# ANALOG_IO.net
KiCad netlist of a schematic drawn in Altium Designer
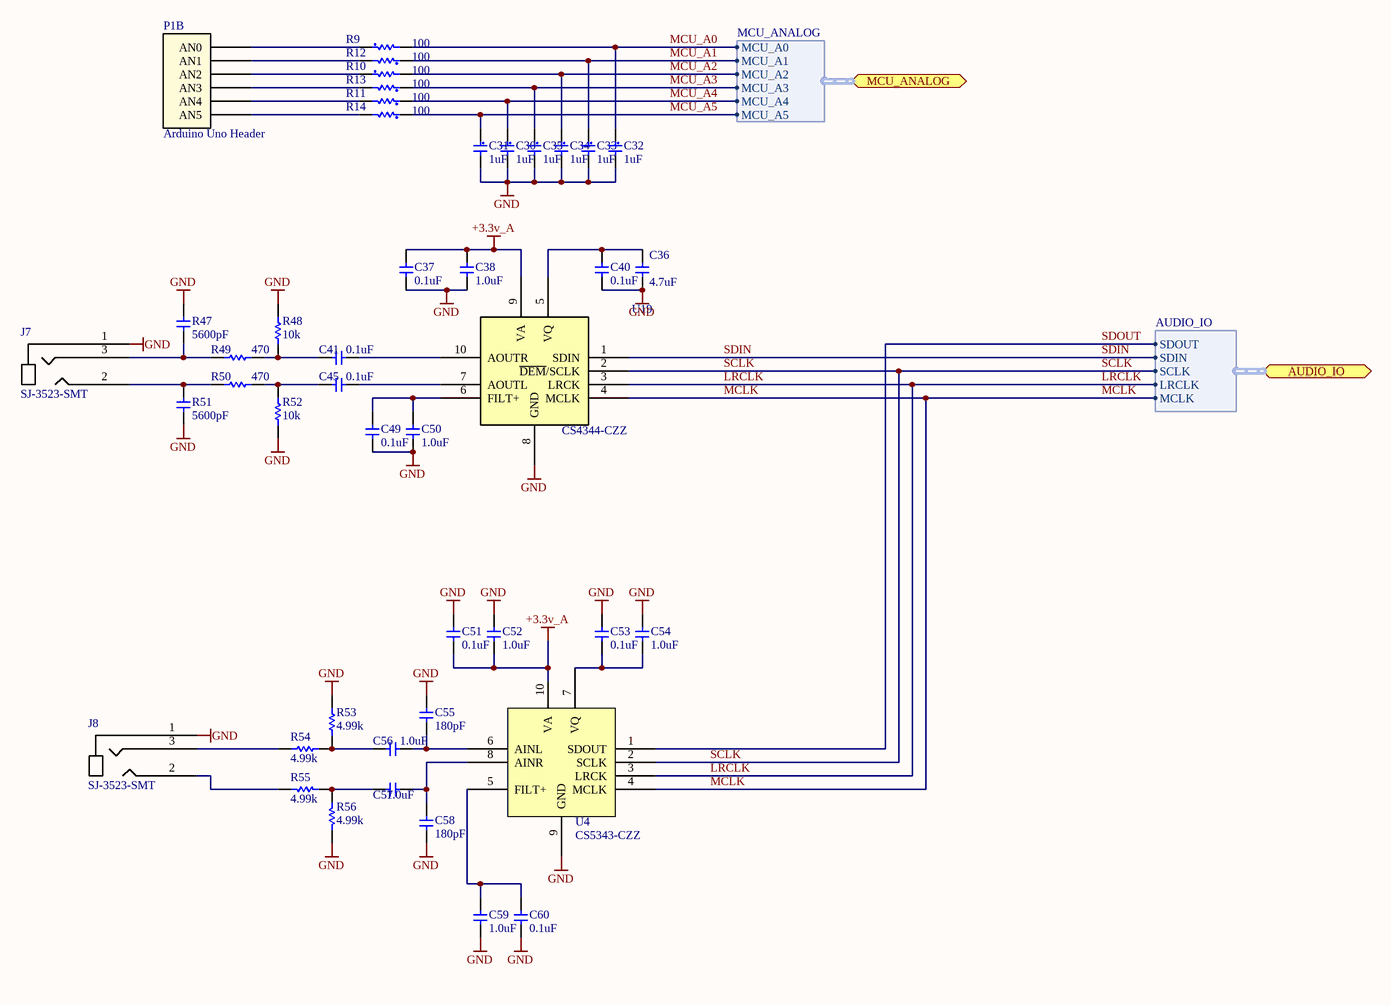
[diagram p0: ANALOG_IO.SchDoc]

(export (version "E")
  (design (tool "Eeschema 10.0.6"))
  (components
    (comp (ref "C30")
      (value "1uF")
      (footprint "C0603")
      (description "CAP CER .1UF 50V 10% X7R 0603")
      (fields
        (field (name "MANUFACTURER") "Murata Electronics North America")
        (field (name "MANUFACTURER PART NUMBER") "GRM188R71H104KA93D")
      )
      (libsource (lib "myGeneral") (part "Cap-Eli"))
    )
    (comp (ref "C31")
      (value "1uF")
      (footprint "C0603")
      (description "CAP CER .1UF 50V 10% X7R 0603")
      (fields
        (field (name "MANUFACTURER") "Murata Electronics North America")
        (field (name "MANUFACTURER PART NUMBER") "GRM188R71H104KA93D")
      )
      (libsource (lib "myGeneral") (part "Cap-Eli"))
    )
    (comp (ref "C32")
      (value "1uF")
      (footprint "C0603")
      (description "CAP CER .1UF 50V 10% X7R 0603")
      (fields
        (field (name "MANUFACTURER") "Murata Electronics North America")
        (field (name "MANUFACTURER PART NUMBER") "GRM188R71H104KA93D")
      )
      (libsource (lib "myGeneral") (part "Cap-Eli"))
    )
    (comp (ref "C33")
      (value "1uF")
      (footprint "C0603")
      (description "CAP CER .1UF 50V 10% X7R 0603")
      (fields
        (field (name "MANUFACTURER") "Murata Electronics North America")
        (field (name "MANUFACTURER PART NUMBER") "GRM188R71H104KA93D")
      )
      (libsource (lib "myGeneral") (part "Cap-Eli"))
    )
    (comp (ref "C34")
      (value "1uF")
      (footprint "C0603")
      (description "CAP CER .1UF 50V 10% X7R 0603")
      (fields
        (field (name "MANUFACTURER") "Murata Electronics North America")
        (field (name "MANUFACTURER PART NUMBER") "GRM188R71H104KA93D")
      )
      (libsource (lib "myGeneral") (part "Cap-Eli"))
    )
    (comp (ref "C35")
      (value "1uF")
      (footprint "C0603")
      (description "CAP CER .1UF 50V 10% X7R 0603")
      (fields
        (field (name "MANUFACTURER") "Murata Electronics North America")
        (field (name "MANUFACTURER PART NUMBER") "GRM188R71H104KA93D")
      )
      (libsource (lib "myGeneral") (part "Cap-Eli"))
    )
    (comp (ref "C36")
      (value "4.7uF")
      (footprint "C0603")
      (description "CAP CER 4.7UF 6.3V X5R 0603")
      (fields
        (field (name "MANUFACTURER") "Murata Electronics North America")
        (field (name "MANUFACTURER PART NUMBER") "GRM188R60J475KE19D")
      )
      (libsource (lib "eCapacitors") (part "GRM188R60J475KE19D"))
    )
    (comp (ref "C37")
      (value "0.1uF")
      (footprint "C0603")
      (description "CAP CER .1UF 50V 10% X7R 0603")
      (fields
        (field (name "MANUFACTURER") "Murata Electronics North America")
        (field (name "MANUFACTURER PART NUMBER") "GRM188R71H104KA93D")
      )
      (libsource (lib "eCapacitors") (part "GRM188R71H104KA93D"))
    )
    (comp (ref "C38")
      (value "1.0uF")
      (footprint "C0805")
      (description "CAP CER 1.0UF 16V 10% X7R 0805")
      (fields
        (field (name "MANUFACTURER") "Murata Electronics North America")
        (field (name "MANUFACTURER PART NUMBER") "GRM21BR71C105KA01L")
      )
      (libsource (lib "eCapacitors") (part "GRM21BR71C105KA01L"))
    )
    (comp (ref "C40")
      (value "0.1uF")
      (footprint "C0603")
      (description "CAP CER .1UF 50V 10% X7R 0603")
      (fields
        (field (name "MANUFACTURER") "Murata Electronics North America")
        (field (name "MANUFACTURER PART NUMBER") "GRM188R71H104KA93D")
      )
      (libsource (lib "eCapacitors") (part "GRM188R71H104KA93D"))
    )
    (comp (ref "C41")
      (value "0.1uF")
      (footprint "C0603")
      (description "CAP CER .1UF 50V 10% X7R 0603")
      (fields
        (field (name "MANUFACTURER") "Murata Electronics North America")
        (field (name "MANUFACTURER PART NUMBER") "GRM188R71H104KA93D")
      )
      (libsource (lib "eCapacitors") (part "GRM188R71H104KA93D"))
    )
    (comp (ref "C45")
      (value "0.1uF")
      (footprint "C0603")
      (description "CAP CER .1UF 50V 10% X7R 0603")
      (fields
        (field (name "MANUFACTURER") "Murata Electronics North America")
        (field (name "MANUFACTURER PART NUMBER") "GRM188R71H104KA93D")
      )
      (libsource (lib "eCapacitors") (part "GRM188R71H104KA93D"))
    )
    (comp (ref "C49")
      (value "0.1uF")
      (footprint "C0603")
      (description "CAP CER .1UF 50V 10% X7R 0603")
      (fields
        (field (name "MANUFACTURER") "Murata Electronics North America")
        (field (name "MANUFACTURER PART NUMBER") "GRM188R71H104KA93D")
      )
      (libsource (lib "eCapacitors") (part "GRM188R71H104KA93D"))
    )
    (comp (ref "C50")
      (value "1.0uF")
      (footprint "C0805")
      (description "CAP CER 1.0UF 16V 10% X7R 0805")
      (fields
        (field (name "MANUFACTURER") "Murata Electronics North America")
        (field (name "MANUFACTURER PART NUMBER") "GRM21BR71C105KA01L")
      )
      (libsource (lib "eCapacitors") (part "GRM21BR71C105KA01L"))
    )
    (comp (ref "C51")
      (value "0.1uF")
      (footprint "C0603")
      (description "CAP CER .1UF 50V 10% X7R 0603")
      (fields
        (field (name "MANUFACTURER") "Murata Electronics North America")
        (field (name "MANUFACTURER PART NUMBER") "GRM188R71H104KA93D")
      )
      (libsource (lib "eCapacitors") (part "GRM188R71H104KA93D"))
    )
    (comp (ref "C52")
      (value "1.0uF")
      (footprint "C0805")
      (description "CAP CER 1.0UF 16V 10% X7R 0805")
      (fields
        (field (name "MANUFACTURER") "Murata Electronics North America")
        (field (name "MANUFACTURER PART NUMBER") "GRM21BR71C105KA01L")
      )
      (libsource (lib "eCapacitors") (part "GRM21BR71C105KA01L"))
    )
    (comp (ref "C53")
      (value "0.1uF")
      (footprint "C0603")
      (description "CAP CER .1UF 50V 10% X7R 0603")
      (fields
        (field (name "MANUFACTURER") "Murata Electronics North America")
        (field (name "MANUFACTURER PART NUMBER") "GRM188R71H104KA93D")
      )
      (libsource (lib "eCapacitors") (part "GRM188R71H104KA93D"))
    )
    (comp (ref "C54")
      (value "1.0uF")
      (footprint "C0805")
      (description "CAP CER 1.0UF 16V 10% X7R 0805")
      (fields
        (field (name "MANUFACTURER") "Murata Electronics North America")
        (field (name "MANUFACTURER PART NUMBER") "GRM21BR71C105KA01L")
      )
      (libsource (lib "eCapacitors") (part "GRM21BR71C105KA01L"))
    )
    (comp (ref "C55")
      (value "180pF")
      (footprint "C0603")
      (description "CAP CER 180PF 50V 5% NP0 0603")
      (fields
        (field (name "MANUFACTURER") "TDK Corporation")
        (field (name "MANUFACTURER PART NUMBER") "C1608C0G1H181J")
      )
      (libsource (lib "eCapacitors") (part "C1608C0G1H181J"))
    )
    (comp (ref "C56")
      (value "1.0uF")
      (footprint "C0805")
      (description "CAP CER 1.0UF 16V 10% X7R 0805")
      (fields
        (field (name "MANUFACTURER") "Murata Electronics North America")
        (field (name "MANUFACTURER PART NUMBER") "GRM21BR71C105KA01L")
      )
      (libsource (lib "eCapacitors") (part "GRM21BR71C105KA01L"))
    )
    (comp (ref "C57")
      (value "1.0uF")
      (footprint "C0805")
      (description "CAP CER 1.0UF 16V 10% X7R 0805")
      (fields
        (field (name "MANUFACTURER") "Murata Electronics North America")
        (field (name "MANUFACTURER PART NUMBER") "GRM21BR71C105KA01L")
      )
      (libsource (lib "eCapacitors") (part "GRM21BR71C105KA01L"))
    )
    (comp (ref "C58")
      (value "180pF")
      (footprint "C0603")
      (description "CAP CER 180PF 50V 5% NP0 0603")
      (fields
        (field (name "MANUFACTURER") "TDK Corporation")
        (field (name "MANUFACTURER PART NUMBER") "C1608C0G1H181J")
      )
      (libsource (lib "eCapacitors") (part "C1608C0G1H181J"))
    )
    (comp (ref "C59")
      (value "1.0uF")
      (footprint "C0805")
      (description "CAP CER 1.0UF 16V 10% X7R 0805")
      (fields
        (field (name "MANUFACTURER") "Murata Electronics North America")
        (field (name "MANUFACTURER PART NUMBER") "GRM21BR71C105KA01L")
      )
      (libsource (lib "eCapacitors") (part "GRM21BR71C105KA01L"))
    )
    (comp (ref "C60")
      (value "0.1uF")
      (footprint "C0603")
      (description "CAP CER .1UF 50V 10% X7R 0603")
      (fields
        (field (name "MANUFACTURER") "Murata Electronics North America")
        (field (name "MANUFACTURER PART NUMBER") "GRM188R71H104KA93D")
      )
      (libsource (lib "eCapacitors") (part "GRM188R71H104KA93D"))
    )
    (comp (ref "J7")
      (value "SJ-3523-SMT")
      (footprint "SJ-3523-SMT")
      (description "CONN AUDIO JACK 3.5MM STEREO SMD")
      (fields (field (name "MANUFACTURER") "CUI Inc") (field (name "SOURCE") "Digikey"))
      (libsource (lib "eConnector") (part "SJ-3523-SMT"))
    )
    (comp (ref "J8")
      (value "SJ-3523-SMT")
      (footprint "SJ-3523-SMT")
      (description "CONN AUDIO JACK 3.5MM STEREO SMD")
      (fields (field (name "MANUFACTURER") "CUI Inc") (field (name "SOURCE") "Digikey"))
      (libsource (lib "eConnector") (part "SJ-3523-SMT"))
    )
    (comp (ref "P1")
      (value "Arduino Uno Header")
      (footprint "Arduino Shield")
      (description "Arduino Duem Header")
      (libsource (lib "eConnector") (part "Arduino Shield"))
    )
    (comp (ref "R9")
      (value "100")
      (footprint "R0603")
      (description "RES 10.0K OHM 1/10W 1% 0603 SMD")
      (fields
        (field (name "MANUFACTURER") "Panasonic - ECG")
        (field (name "MANUFACTURER PART NUMBER") "ERJ-3EKF1002V")
      )
      (libsource (lib "myGeneral") (part "Res-Eli"))
    )
    (comp (ref "R10")
      (value "100")
      (footprint "R0603")
      (description "RES 10.0K OHM 1/10W 1% 0603 SMD")
      (fields
        (field (name "MANUFACTURER") "Panasonic - ECG")
        (field (name "MANUFACTURER PART NUMBER") "ERJ-3EKF1002V")
      )
      (libsource (lib "myGeneral") (part "Res-Eli"))
    )
    (comp (ref "R11")
      (value "100")
      (footprint "R0603")
      (description "RES 10.0K OHM 1/10W 1% 0603 SMD")
      (fields
        (field (name "MANUFACTURER") "Panasonic - ECG")
        (field (name "MANUFACTURER PART NUMBER") "ERJ-3EKF1002V")
      )
      (libsource (lib "myGeneral") (part "Res-Eli"))
    )
    (comp (ref "R12")
      (value "100")
      (footprint "R0603")
      (description "RES 10.0K OHM 1/10W 1% 0603 SMD")
      (fields
        (field (name "MANUFACTURER") "Panasonic - ECG")
        (field (name "MANUFACTURER PART NUMBER") "ERJ-3EKF1002V")
      )
      (libsource (lib "myGeneral") (part "Res-Eli"))
    )
    (comp (ref "R13")
      (value "100")
      (footprint "R0603")
      (description "RES 10.0K OHM 1/10W 1% 0603 SMD")
      (fields
        (field (name "MANUFACTURER") "Panasonic - ECG")
        (field (name "MANUFACTURER PART NUMBER") "ERJ-3EKF1002V")
      )
      (libsource (lib "myGeneral") (part "Res-Eli"))
    )
    (comp (ref "R14")
      (value "100")
      (footprint "R0603")
      (description "RES 10.0K OHM 1/10W 1% 0603 SMD")
      (fields
        (field (name "MANUFACTURER") "Panasonic - ECG")
        (field (name "MANUFACTURER PART NUMBER") "ERJ-3EKF1002V")
      )
      (libsource (lib "myGeneral") (part "Res-Eli"))
    )
    (comp (ref "R47")
      (value "5600pF")
      (footprint "C0603")
      (description "CAP CER 5600PF 50V 10% X7R 0603")
      (fields
        (field (name "MANUFACTURER") "Murata Electronics North America")
        (field (name "MANUFACTURER PART NUMBER") "GRM188R71H562KA01D")
      )
      (libsource (lib "eCapacitors") (part "GRM188R71H562KA01D"))
    )
    (comp (ref "R48")
      (value "10k")
      (footprint "R0603")
      (description "RES 10.0K OHM 1/10W 1% 0603 SMD")
      (fields
        (field (name "MANUFACTURER") "Panasonic - ECG")
        (field (name "TOLERANCE") "±1%")
        (field (name "SOURCE") "Digikey")
      )
      (libsource (lib "eRCL") (part "ERJ-3EKF1002V"))
    )
    (comp (ref "R49")
      (value "470")
      (footprint "R0603")
      (description "RES 470 OHM 1/10W 1% 0603 SMD")
      (fields
        (field (name "MANUFACTURER") "Panasonic - ECG")
        (field (name "MANUFACTURER PART NUMBER") "ERJ-3EKF4700V")
      )
      (libsource (lib "eResistors") (part "ERJ-3EKF4700V"))
    )
    (comp (ref "R50")
      (value "470")
      (footprint "R0603")
      (description "RES 470 OHM 1/10W 1% 0603 SMD")
      (fields
        (field (name "MANUFACTURER") "Panasonic - ECG")
        (field (name "MANUFACTURER PART NUMBER") "ERJ-3EKF4700V")
      )
      (libsource (lib "eResistors") (part "ERJ-3EKF4700V"))
    )
    (comp (ref "R51")
      (value "5600pF")
      (footprint "C0603")
      (description "CAP CER 5600PF 50V 10% X7R 0603")
      (fields
        (field (name "MANUFACTURER") "Murata Electronics North America")
        (field (name "MANUFACTURER PART NUMBER") "GRM188R71H562KA01D")
      )
      (libsource (lib "eCapacitors") (part "GRM188R71H562KA01D"))
    )
    (comp (ref "R52")
      (value "10k")
      (footprint "R0603")
      (description "RES 10.0K OHM 1/10W 1% 0603 SMD")
      (fields
        (field (name "MANUFACTURER") "Panasonic - ECG")
        (field (name "TOLERANCE") "±1%")
        (field (name "SOURCE") "Digikey")
      )
      (libsource (lib "eRCL") (part "ERJ-3EKF1002V"))
    )
    (comp (ref "R53")
      (value "4.99k")
      (footprint "R0603")
      (description "RES 4.99K OHM 1/10W 1% 0603 SMD")
      (fields
        (field (name "MANUFACTURER") "Panasonic - ECG")
        (field (name "MANUFACTURER PART NUMBER") "ERJ-3EKF4991V")
      )
      (libsource (lib "eResistors") (part "ERJ-3EKF4991V"))
    )
    (comp (ref "R54")
      (value "4.99k")
      (footprint "R0603")
      (description "RES 4.99K OHM 1/10W 1% 0603 SMD")
      (fields
        (field (name "MANUFACTURER") "Panasonic - ECG")
        (field (name "MANUFACTURER PART NUMBER") "ERJ-3EKF4991V")
      )
      (libsource (lib "eResistors") (part "ERJ-3EKF4991V"))
    )
    (comp (ref "R55")
      (value "4.99k")
      (footprint "R0603")
      (description "RES 4.99K OHM 1/10W 1% 0603 SMD")
      (fields
        (field (name "MANUFACTURER") "Panasonic - ECG")
        (field (name "MANUFACTURER PART NUMBER") "ERJ-3EKF4991V")
      )
      (libsource (lib "eResistors") (part "ERJ-3EKF4991V"))
    )
    (comp (ref "R56")
      (value "4.99k")
      (footprint "R0603")
      (description "RES 4.99K OHM 1/10W 1% 0603 SMD")
      (fields
        (field (name "MANUFACTURER") "Panasonic - ECG")
        (field (name "MANUFACTURER PART NUMBER") "ERJ-3EKF4991V")
      )
      (libsource (lib "eResistors") (part "ERJ-3EKF4991V"))
    )
    (comp (ref "U4")
      (value "CS5343-CZZ")
      (footprint "TSSOP10")
      (description "IC ADC AUD 98DB 108KHZ 10-TSSOP")
      (fields (field (name "MANUFACTURER") "rus Logic Inc") (field (name "SOURCE") "Digikey"))
      (libsource (lib "EE417") (part "CS5343-CZZ"))
    )
    (comp (ref "U19")
      (value "CS4344-CZZ")
      (footprint "TSSOP10")
      (description "IC DAC STER 24BIT 192KHZ 10TSSOP")
      (fields (field (name "MANUFACTURER") "rus Logic Inc") (field (name "SOURCE") "Digikey"))
      (libsource (lib "eIC") (part "CS4344-CZZ"))
    )
  )
  (nets
    (net (code "3") (name "+3.3v_A") (class "Default")
      (node (ref "C37") (pin "2") (pinfunction "2_2") (pintype "passive"))
      (node (ref "C38") (pin "2") (pinfunction "2_2") (pintype "passive"))
      (node (ref "C51") (pin "1") (pinfunction "1_1") (pintype "passive"))
      (node (ref "C52") (pin "1") (pinfunction "1_1") (pintype "passive"))
      (node (ref "U19") (pin "9") (pinfunction "VA_9") (pintype "passive"))
      (node (ref "U4") (pin "10") (pinfunction "VA_10") (pintype "passive"))
    )
    (net (code "4") (name "/LRCLK") (class "Default")
      (node (ref "U19") (pin "3") (pinfunction "LRCK_3") (pintype "passive"))
      (node (ref "U4") (pin "3") (pinfunction "LRCK_3") (pintype "passive"))
    )
    (net (code "5") (name "/MCLK") (class "Default")
      (node (ref "U19") (pin "4") (pinfunction "MCLK_4") (pintype "passive"))
      (node (ref "U4") (pin "4") (pinfunction "MCLK_4") (pintype "passive"))
    )
    (net (code "6") (name "/MCU_A0") (class "Default")
      (node (ref "C32") (pin "1") (pinfunction "1_1") (pintype "passive"))
      (node (ref "R9") (pin "2") (pinfunction "2_2") (pintype "passive"))
    )
    (net (code "7") (name "/MCU_A1") (class "Default")
      (node (ref "C33") (pin "1") (pinfunction "1_1") (pintype "passive"))
      (node (ref "R12") (pin "1") (pinfunction "1_1") (pintype "passive"))
    )
    (net (code "8") (name "/MCU_A2") (class "Default")
      (node (ref "C34") (pin "1") (pinfunction "1_1") (pintype "passive"))
      (node (ref "R10") (pin "2") (pinfunction "2_2") (pintype "passive"))
    )
    (net (code "9") (name "/MCU_A3") (class "Default")
      (node (ref "C35") (pin "1") (pinfunction "1_1") (pintype "passive"))
      (node (ref "R13") (pin "1") (pinfunction "1_1") (pintype "passive"))
    )
    (net (code "10") (name "/MCU_A4") (class "Default")
      (node (ref "C30") (pin "1") (pinfunction "1_1") (pintype "passive"))
      (node (ref "R11") (pin "1") (pinfunction "1_1") (pintype "passive"))
    )
    (net (code "11") (name "/MCU_A5") (class "Default")
      (node (ref "C31") (pin "1") (pinfunction "1_1") (pintype "passive"))
      (node (ref "R14") (pin "1") (pinfunction "1_1") (pintype "passive"))
    )
    (net (code "12") (name "/SCLK") (class "Default")
      (node (ref "U19") (pin "2") (pinfunction "~{DEM}/SCLK_2") (pintype "passive"))
      (node (ref "U4") (pin "2") (pinfunction "SCLK_2") (pintype "passive"))
    )
    (net (code "13") (name "/SDIN") (class "Default")
      (node (ref "U19") (pin "1") (pinfunction "SDIN_1") (pintype "passive"))
    )
    (net (code "14") (name "/SDOUT") (class "Default")
      (node (ref "U4") (pin "1") (pinfunction "SDOUT_1") (pintype "passive"))
    )
    (net (code "17") (name "GND") (class "Default")
      (node (ref "C30") (pin "2") (pinfunction "2_2") (pintype "passive"))
      (node (ref "C31") (pin "2") (pinfunction "2_2") (pintype "passive"))
      (node (ref "C32") (pin "2") (pinfunction "2_2") (pintype "passive"))
      (node (ref "C33") (pin "2") (pinfunction "2_2") (pintype "passive"))
      (node (ref "C34") (pin "2") (pinfunction "2_2") (pintype "passive"))
      (node (ref "C35") (pin "2") (pinfunction "2_2") (pintype "passive"))
      (node (ref "C36") (pin "1") (pinfunction "1_1") (pintype "passive"))
      (node (ref "C37") (pin "1") (pinfunction "1_1") (pintype "passive"))
      (node (ref "C38") (pin "1") (pinfunction "1_1") (pintype "passive"))
      (node (ref "C40") (pin "1") (pinfunction "1_1") (pintype "passive"))
      (node (ref "C49") (pin "1") (pinfunction "1_1") (pintype "passive"))
      (node (ref "C50") (pin "1") (pinfunction "1_1") (pintype "passive"))
      (node (ref "C51") (pin "2") (pinfunction "2_2") (pintype "passive"))
      (node (ref "C52") (pin "2") (pinfunction "2_2") (pintype "passive"))
      (node (ref "C53") (pin "2") (pinfunction "2_2") (pintype "passive"))
      (node (ref "C54") (pin "2") (pinfunction "2_2") (pintype "passive"))
      (node (ref "C55") (pin "2") (pinfunction "2_2") (pintype "passive"))
      (node (ref "C58") (pin "1") (pinfunction "1_1") (pintype "passive"))
      (node (ref "C59") (pin "2") (pinfunction "2_2") (pintype "passive"))
      (node (ref "C60") (pin "2") (pinfunction "2_2") (pintype "passive"))
      (node (ref "J7") (pin "1") (pinfunction "1_1") (pintype "passive"))
      (node (ref "J8") (pin "1") (pinfunction "1_1") (pintype "passive"))
      (node (ref "R47") (pin "2") (pinfunction "2_2") (pintype "passive"))
      (node (ref "R48") (pin "1") (pinfunction "1_1") (pintype "passive"))
      (node (ref "R51") (pin "1") (pinfunction "1_1") (pintype "passive"))
      (node (ref "R52") (pin "2") (pinfunction "2_2") (pintype "passive"))
      (node (ref "R53") (pin "2") (pinfunction "2_2") (pintype "passive"))
      (node (ref "R56") (pin "2") (pinfunction "2_2") (pintype "passive"))
      (node (ref "U19") (pin "8") (pinfunction "GND_8") (pintype "passive"))
      (node (ref "U4") (pin "9") (pinfunction "GND_9") (pintype "passive"))
    )
    (net (code "18") (name "Net-(C41-Pad2)") (class "Default")
      (node (ref "C41") (pin "2") (pinfunction "2_2") (pintype "passive"))
      (node (ref "R48") (pin "2") (pinfunction "2_2") (pintype "passive"))
      (node (ref "R49") (pin "1") (pinfunction "1_1") (pintype "passive"))
    )
    (net (code "19") (name "Net-(C45-Pad2)") (class "Default")
      (node (ref "C45") (pin "2") (pinfunction "2_2") (pintype "passive"))
      (node (ref "R50") (pin "1") (pinfunction "1_1") (pintype "passive"))
      (node (ref "R52") (pin "1") (pinfunction "1_1") (pintype "passive"))
    )
    (net (code "20") (name "Net-(C56-Pad1)") (class "Default")
      (node (ref "C56") (pin "1") (pinfunction "1_1") (pintype "passive"))
      (node (ref "R53") (pin "1") (pinfunction "1_1") (pintype "passive"))
      (node (ref "R54") (pin "2") (pinfunction "2_2") (pintype "passive"))
    )
    (net (code "21") (name "Net-(C57-Pad1)") (class "Default")
      (node (ref "C57") (pin "1") (pinfunction "1_1") (pintype "passive"))
      (node (ref "R55") (pin "2") (pinfunction "2_2") (pintype "passive"))
      (node (ref "R56") (pin "1") (pinfunction "1_1") (pintype "passive"))
    )
    (net (code "22") (name "Net-(J7-Pad2)") (class "Default")
      (node (ref "J7") (pin "2") (pinfunction "2_2") (pintype "passive"))
      (node (ref "R50") (pin "2") (pinfunction "2_2") (pintype "passive"))
      (node (ref "R51") (pin "2") (pinfunction "2_2") (pintype "passive"))
    )
    (net (code "23") (name "Net-(J7-Pad3)") (class "Default")
      (node (ref "J7") (pin "3") (pinfunction "3_3") (pintype "passive"))
      (node (ref "R47") (pin "1") (pinfunction "1_1") (pintype "passive"))
      (node (ref "R49") (pin "2") (pinfunction "2_2") (pintype "passive"))
    )
    (net (code "24") (name "Net-(J8-Pad2)") (class "Default")
      (node (ref "J8") (pin "2") (pinfunction "2_2") (pintype "passive"))
      (node (ref "R55") (pin "1") (pinfunction "1_1") (pintype "passive"))
    )
    (net (code "25") (name "Net-(J8-Pad3)") (class "Default")
      (node (ref "J8") (pin "3") (pinfunction "3_3") (pintype "passive"))
      (node (ref "R54") (pin "1") (pinfunction "1_1") (pintype "passive"))
    )
    (net (code "26") (name "Net-(P1B-AN0)") (class "Default")
      (node (ref "P1") (pin "B1") (pinfunction "AN0_B1") (pintype "passive"))
      (node (ref "R9") (pin "1") (pinfunction "1_1") (pintype "passive"))
    )
    (net (code "27") (name "Net-(P1B-AN1)") (class "Default")
      (node (ref "P1") (pin "B2") (pinfunction "AN1_B2") (pintype "passive"))
      (node (ref "R12") (pin "2") (pinfunction "2_2") (pintype "passive"))
    )
    (net (code "28") (name "Net-(P1B-AN2)") (class "Default")
      (node (ref "P1") (pin "B3") (pinfunction "AN2_B3") (pintype "passive"))
      (node (ref "R10") (pin "1") (pinfunction "1_1") (pintype "passive"))
    )
    (net (code "29") (name "Net-(P1B-AN3)") (class "Default")
      (node (ref "P1") (pin "B4") (pinfunction "AN3_B4") (pintype "passive"))
      (node (ref "R13") (pin "2") (pinfunction "2_2") (pintype "passive"))
    )
    (net (code "30") (name "Net-(P1B-AN4)") (class "Default")
      (node (ref "P1") (pin "B5") (pinfunction "AN4_B5") (pintype "passive"))
      (node (ref "R11") (pin "2") (pinfunction "2_2") (pintype "passive"))
    )
    (net (code "31") (name "Net-(P1B-AN5)") (class "Default")
      (node (ref "P1") (pin "B6") (pinfunction "AN5_B6") (pintype "passive"))
      (node (ref "R14") (pin "2") (pinfunction "2_2") (pintype "passive"))
    )
    (net (code "32") (name "Net-(U4-AINL)") (class "Default")
      (node (ref "C55") (pin "1") (pinfunction "1_1") (pintype "passive"))
      (node (ref "C56") (pin "2") (pinfunction "2_2") (pintype "passive"))
      (node (ref "U4") (pin "6") (pinfunction "AINL_6") (pintype "passive"))
    )
    (net (code "33") (name "Net-(U4-AINR)") (class "Default")
      (node (ref "C57") (pin "2") (pinfunction "2_2") (pintype "passive"))
      (node (ref "C58") (pin "2") (pinfunction "2_2") (pintype "passive"))
      (node (ref "U4") (pin "8") (pinfunction "AINR_8") (pintype "passive"))
    )
    (net (code "34") (name "Net-(U4-FILT+)") (class "Default")
      (node (ref "C59") (pin "1") (pinfunction "1_1") (pintype "passive"))
      (node (ref "C60") (pin "1") (pinfunction "1_1") (pintype "passive"))
      (node (ref "U4") (pin "5") (pinfunction "FILT+_5") (pintype "passive"))
    )
    (net (code "35") (name "Net-(U4-VQ)") (class "Default")
      (node (ref "C53") (pin "1") (pinfunction "1_1") (pintype "passive"))
      (node (ref "C54") (pin "1") (pinfunction "1_1") (pintype "passive"))
      (node (ref "U4") (pin "7") (pinfunction "VQ_7") (pintype "passive"))
    )
    (net (code "36") (name "Net-(U19-AOUTL)") (class "Default")
      (node (ref "C45") (pin "1") (pinfunction "1_1") (pintype "passive"))
      (node (ref "U19") (pin "7") (pinfunction "AOUTL_7") (pintype "passive"))
    )
    (net (code "37") (name "Net-(U19-AOUTR)") (class "Default")
      (node (ref "C41") (pin "1") (pinfunction "1_1") (pintype "passive"))
      (node (ref "U19") (pin "10") (pinfunction "AOUTR_10") (pintype "passive"))
    )
    (net (code "38") (name "Net-(U19-FILT+)") (class "Default")
      (node (ref "C49") (pin "2") (pinfunction "2_2") (pintype "passive"))
      (node (ref "C50") (pin "2") (pinfunction "2_2") (pintype "passive"))
      (node (ref "U19") (pin "6") (pinfunction "FILT+_6") (pintype "passive"))
    )
    (net (code "39") (name "Net-(U19-VQ)") (class "Default")
      (node (ref "C36") (pin "2") (pinfunction "2_2") (pintype "passive"))
      (node (ref "C40") (pin "2") (pinfunction "2_2") (pintype "passive"))
      (node (ref "U19") (pin "5") (pinfunction "VQ_5") (pintype "passive"))
    )
  )
)
